# nodeMcu_ir_gateway_03_back.net
KiCad netlist of a schematic drawn in EAGLE
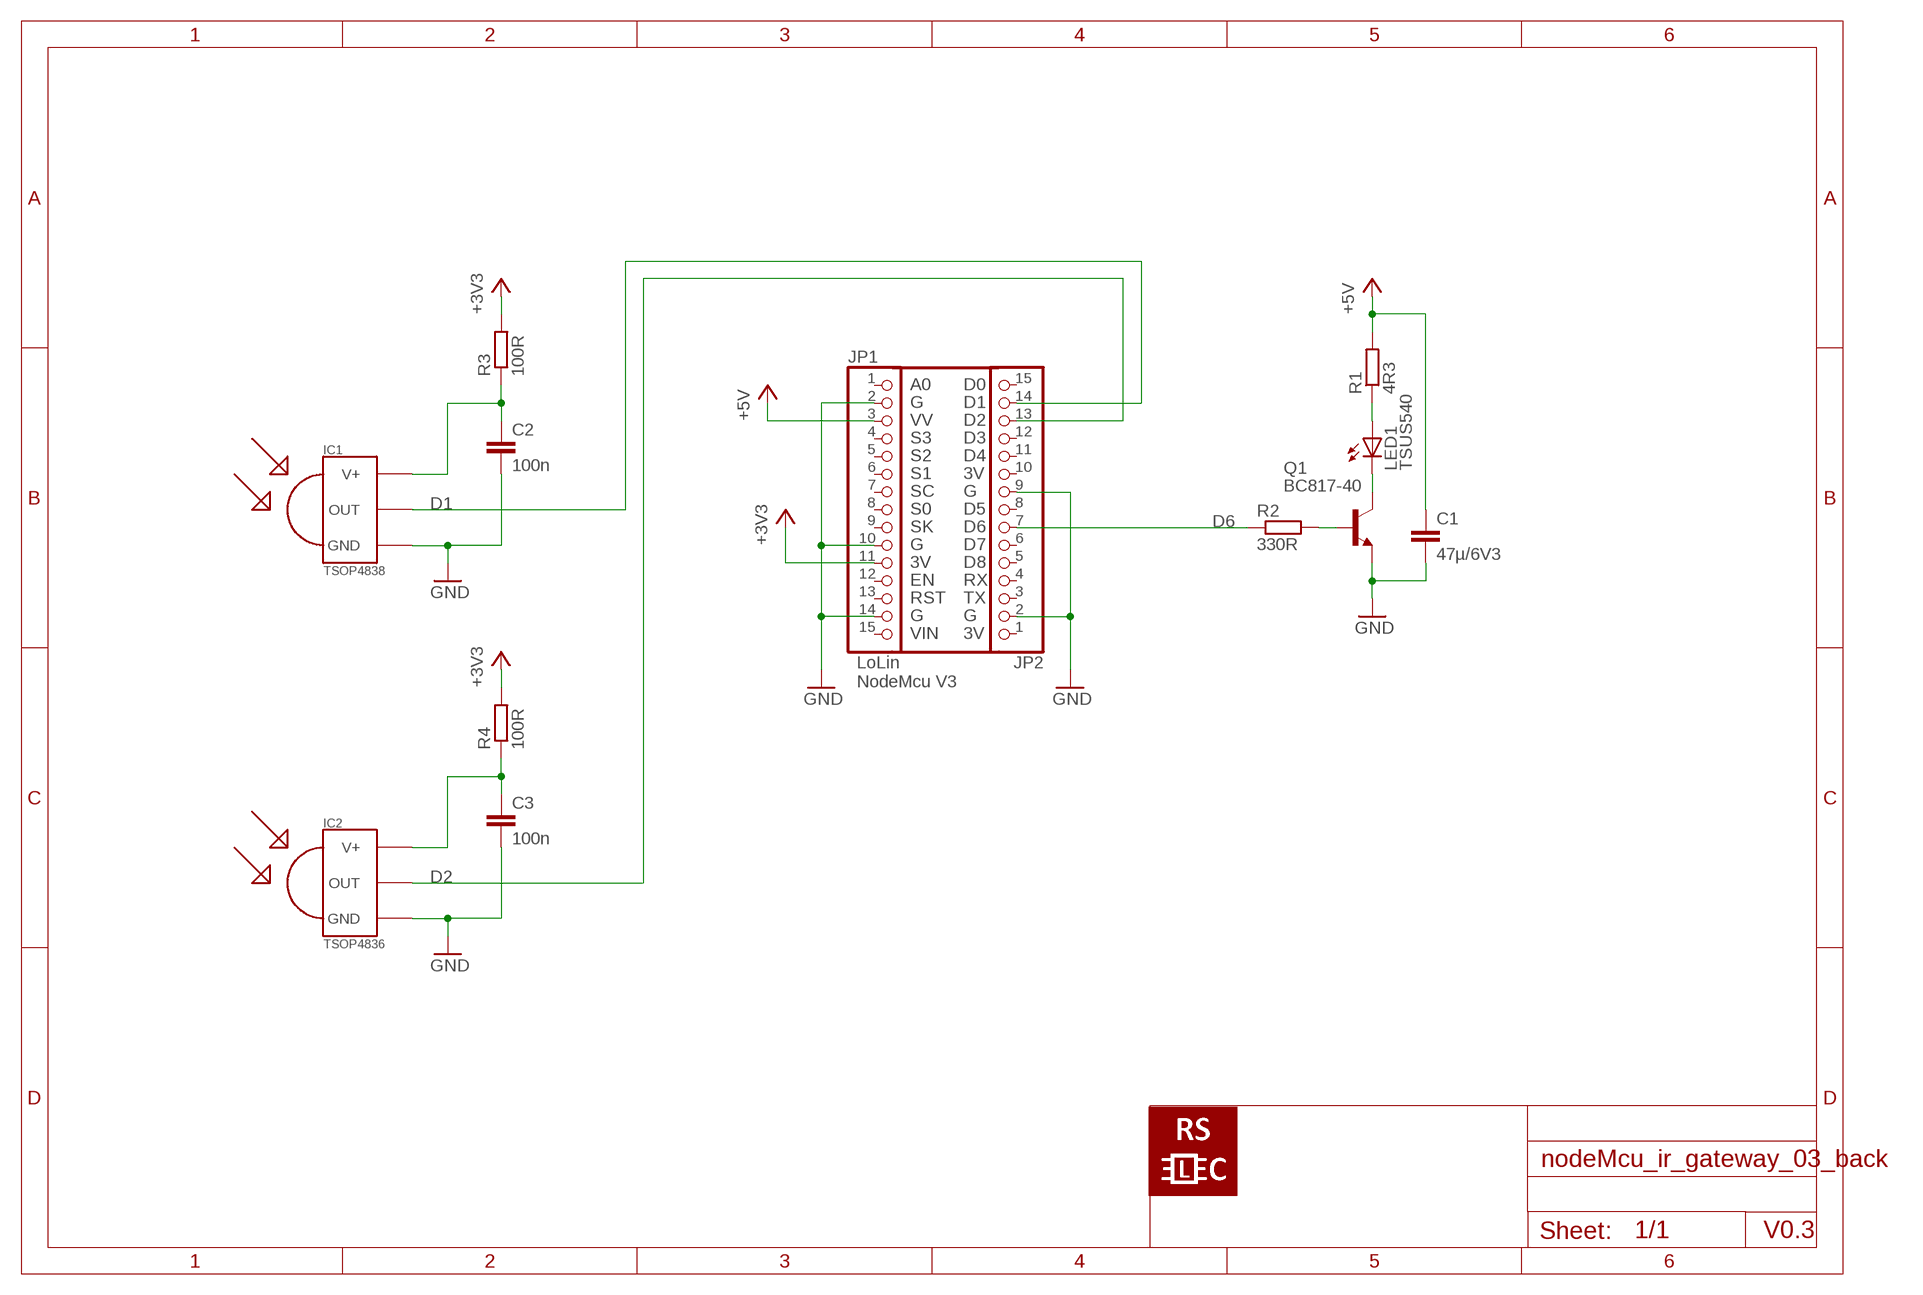
[diagram p0: schematic, sheet 1]

(export (version "E")
  (design (tool "Eeschema 10.0.6"))
  (components
    (comp (ref "C1")
      (value "47µ/6V3")
      (footprint "eagle-import:C1206")
      (libsource (lib "eagle-import") (part "C-EUC1206"))
    )
    (comp (ref "C2")
      (value "100n")
      (footprint "eagle-import:C0805")
      (libsource (lib "eagle-import") (part "C-EUC0805"))
    )
    (comp (ref "C3")
      (value "100n")
      (footprint "eagle-import:C0805")
      (libsource (lib "eagle-import") (part "C-EUC0805"))
    )
    (comp (ref "IC1")
      (value "TSOP4838")
      (footprint "eagle-import:TSOP18XX_H")
      (libsource (lib "eagle-import") (part "TSOP4838H"))
    )
    (comp (ref "IC2")
      (value "TSOP4836")
      (footprint "eagle-import:TSOP18XX_H")
      (libsource (lib "eagle-import") (part "TSOP4838H"))
    )
    (comp (ref "JP1")
      (value "PINHD-1X15_2.54")
      (footprint "eagle-import:1X15")
      (libsource (lib "eagle-import") (part "PINHD-1X15_2.54"))
    )
    (comp (ref "JP2")
      (value "PINHD-1X15_2.54")
      (footprint "eagle-import:1X15")
      (libsource (lib "eagle-import") (part "PINHD-1X15_2.54"))
    )
    (comp (ref "LED1")
      (value "TSUS540")
      (footprint "eagle-import:LED5MM")
      (libsource (lib "eagle-import") (part "LED5MM"))
    )
    (comp (ref "LOGO1")
      (value "LOGO400N")
      (footprint "eagle-import:LOGO_400N")
      (libsource (lib "eagle-import") (part "LOGO400N"))
    )
    (comp (ref "Q1")
      (value "BC817-40")
      (footprint "eagle-import:SOT23-BEC")
      (libsource (lib "eagle-import") (part "BC817SMD-40"))
    )
    (comp (ref "R1")
      (value "4R3")
      (footprint "eagle-import:0207_10")
      (libsource (lib "eagle-import") (part "R-EU_0207/10"))
    )
    (comp (ref "R2")
      (value "330R")
      (footprint "eagle-import:R0805")
      (libsource (lib "eagle-import") (part "R-EU_R0805"))
    )
    (comp (ref "R3")
      (value "100R")
      (footprint "eagle-import:R0805")
      (libsource (lib "eagle-import") (part "R-EU_R0805"))
    )
    (comp (ref "R4")
      (value "100R")
      (footprint "eagle-import:R0805")
      (libsource (lib "eagle-import") (part "R-EU_R0805"))
    )
  )
  (nets
    (net (code "1") (name "+3V3") (class "Default")
      (node (ref "JP1") (pin "11") (pinfunction "11_11") (pintype "passive"))
      (node (ref "R3") (pin "2") (pinfunction "2_2") (pintype "passive"))
      (node (ref "R4") (pin "2") (pinfunction "2_2") (pintype "passive"))
    )
    (net (code "2") (name "+5V") (class "Default")
      (node (ref "C1") (pin "1") (pinfunction "1_1") (pintype "passive"))
      (node (ref "JP1") (pin "3") (pinfunction "3_3") (pintype "passive"))
      (node (ref "R1") (pin "2") (pinfunction "2_2") (pintype "passive"))
    )
    (net (code "3") (name "/D1") (class "Default")
      (node (ref "IC1") (pin "OUT") (pinfunction "OUT_OUT") (pintype "bidirectional"))
      (node (ref "JP2") (pin "14") (pinfunction "14_14") (pintype "passive"))
    )
    (net (code "4") (name "/D2") (class "Default")
      (node (ref "IC2") (pin "OUT") (pinfunction "OUT_OUT") (pintype "bidirectional"))
      (node (ref "JP2") (pin "13") (pinfunction "13_13") (pintype "passive"))
    )
    (net (code "5") (name "/D6") (class "Default")
      (node (ref "JP2") (pin "7") (pinfunction "7_7") (pintype "passive"))
      (node (ref "R2") (pin "1") (pinfunction "1_1") (pintype "passive"))
    )
    (net (code "6") (name "GND") (class "Default")
      (node (ref "C1") (pin "2") (pinfunction "2_2") (pintype "passive"))
      (node (ref "C2") (pin "2") (pinfunction "2_2") (pintype "passive"))
      (node (ref "C3") (pin "2") (pinfunction "2_2") (pintype "passive"))
      (node (ref "IC1") (pin "GND") (pinfunction "GND_GND") (pintype "bidirectional"))
      (node (ref "IC2") (pin "GND") (pinfunction "GND_GND") (pintype "bidirectional"))
      (node (ref "JP1") (pin "10") (pinfunction "10_10") (pintype "passive"))
      (node (ref "JP1") (pin "14") (pinfunction "14_14") (pintype "passive"))
      (node (ref "JP1") (pin "2") (pinfunction "2_2") (pintype "passive"))
      (node (ref "JP2") (pin "2") (pinfunction "2_2") (pintype "passive"))
      (node (ref "JP2") (pin "9") (pinfunction "9_9") (pintype "passive"))
      (node (ref "Q1") (pin "E") (pinfunction "E_E") (pintype "passive"))
    )
    (net (code "7") (name "Net-(IC1-V+)") (class "Default")
      (node (ref "C2") (pin "1") (pinfunction "1_1") (pintype "passive"))
      (node (ref "IC1") (pin "VCC") (pinfunction "V+_VCC") (pintype "bidirectional"))
      (node (ref "R3") (pin "1") (pinfunction "1_1") (pintype "passive"))
    )
    (net (code "8") (name "Net-(IC2-V+)") (class "Default")
      (node (ref "C3") (pin "1") (pinfunction "1_1") (pintype "passive"))
      (node (ref "IC2") (pin "VCC") (pinfunction "V+_VCC") (pintype "bidirectional"))
      (node (ref "R4") (pin "1") (pinfunction "1_1") (pintype "passive"))
    )
    (net (code "9") (name "Net-(LED1-C)") (class "Default")
      (node (ref "LED1") (pin "K") (pinfunction "C_K") (pintype "passive"))
      (node (ref "Q1") (pin "C") (pinfunction "C_C") (pintype "passive"))
    )
    (net (code "10") (name "Net-(LED1-PadA)") (class "Default")
      (node (ref "LED1") (pin "A") (pinfunction "A_A") (pintype "passive"))
      (node (ref "R1") (pin "1") (pinfunction "1_1") (pintype "passive"))
    )
    (net (code "11") (name "Net-(Q1-PadB)") (class "Default")
      (node (ref "Q1") (pin "B") (pinfunction "B_B") (pintype "passive"))
      (node (ref "R2") (pin "2") (pinfunction "2_2") (pintype "passive"))
    )
    (net (code "12") (name "unconnected-(JP1-Pad1)") (class "Default")
      (node (ref "JP1") (pin "1") (pinfunction "1_1") (pintype "passive"))
    )
    (net (code "13") (name "unconnected-(JP1-Pad4)") (class "Default")
      (node (ref "JP1") (pin "4") (pinfunction "4_4") (pintype "passive"))
    )
    (net (code "14") (name "unconnected-(JP1-Pad5)") (class "Default")
      (node (ref "JP1") (pin "5") (pinfunction "5_5") (pintype "passive"))
    )
    (net (code "15") (name "unconnected-(JP1-Pad6)") (class "Default")
      (node (ref "JP1") (pin "6") (pinfunction "6_6") (pintype "passive"))
    )
    (net (code "16") (name "unconnected-(JP1-Pad7)") (class "Default")
      (node (ref "JP1") (pin "7") (pinfunction "7_7") (pintype "passive"))
    )
    (net (code "17") (name "unconnected-(JP1-Pad8)") (class "Default")
      (node (ref "JP1") (pin "8") (pinfunction "8_8") (pintype "passive"))
    )
    (net (code "18") (name "unconnected-(JP1-Pad9)") (class "Default")
      (node (ref "JP1") (pin "9") (pinfunction "9_9") (pintype "passive"))
    )
    (net (code "19") (name "unconnected-(JP1-Pad12)") (class "Default")
      (node (ref "JP1") (pin "12") (pinfunction "12_12") (pintype "passive"))
    )
    (net (code "20") (name "unconnected-(JP1-Pad13)") (class "Default")
      (node (ref "JP1") (pin "13") (pinfunction "13_13") (pintype "passive"))
    )
    (net (code "21") (name "unconnected-(JP1-Pad15)") (class "Default")
      (node (ref "JP1") (pin "15") (pinfunction "15_15") (pintype "passive"))
    )
    (net (code "22") (name "unconnected-(JP2-Pad1)") (class "Default")
      (node (ref "JP2") (pin "1") (pinfunction "1_1") (pintype "passive"))
    )
    (net (code "23") (name "unconnected-(JP2-Pad3)") (class "Default")
      (node (ref "JP2") (pin "3") (pinfunction "3_3") (pintype "passive"))
    )
    (net (code "24") (name "unconnected-(JP2-Pad4)") (class "Default")
      (node (ref "JP2") (pin "4") (pinfunction "4_4") (pintype "passive"))
    )
    (net (code "25") (name "unconnected-(JP2-Pad5)") (class "Default")
      (node (ref "JP2") (pin "5") (pinfunction "5_5") (pintype "passive"))
    )
    (net (code "26") (name "unconnected-(JP2-Pad6)") (class "Default")
      (node (ref "JP2") (pin "6") (pinfunction "6_6") (pintype "passive"))
    )
    (net (code "27") (name "unconnected-(JP2-Pad8)") (class "Default")
      (node (ref "JP2") (pin "8") (pinfunction "8_8") (pintype "passive"))
    )
    (net (code "28") (name "unconnected-(JP2-Pad10)") (class "Default")
      (node (ref "JP2") (pin "10") (pinfunction "10_10") (pintype "passive"))
    )
    (net (code "29") (name "unconnected-(JP2-Pad11)") (class "Default")
      (node (ref "JP2") (pin "11") (pinfunction "11_11") (pintype "passive"))
    )
    (net (code "30") (name "unconnected-(JP2-Pad12)") (class "Default")
      (node (ref "JP2") (pin "12") (pinfunction "12_12") (pintype "passive"))
    )
    (net (code "31") (name "unconnected-(JP2-Pad15)") (class "Default")
      (node (ref "JP2") (pin "15") (pinfunction "15_15") (pintype "passive"))
    )
  )
)
